# ProxSensorType1.net
KiCad netlist of a schematic drawn in Altium Designer
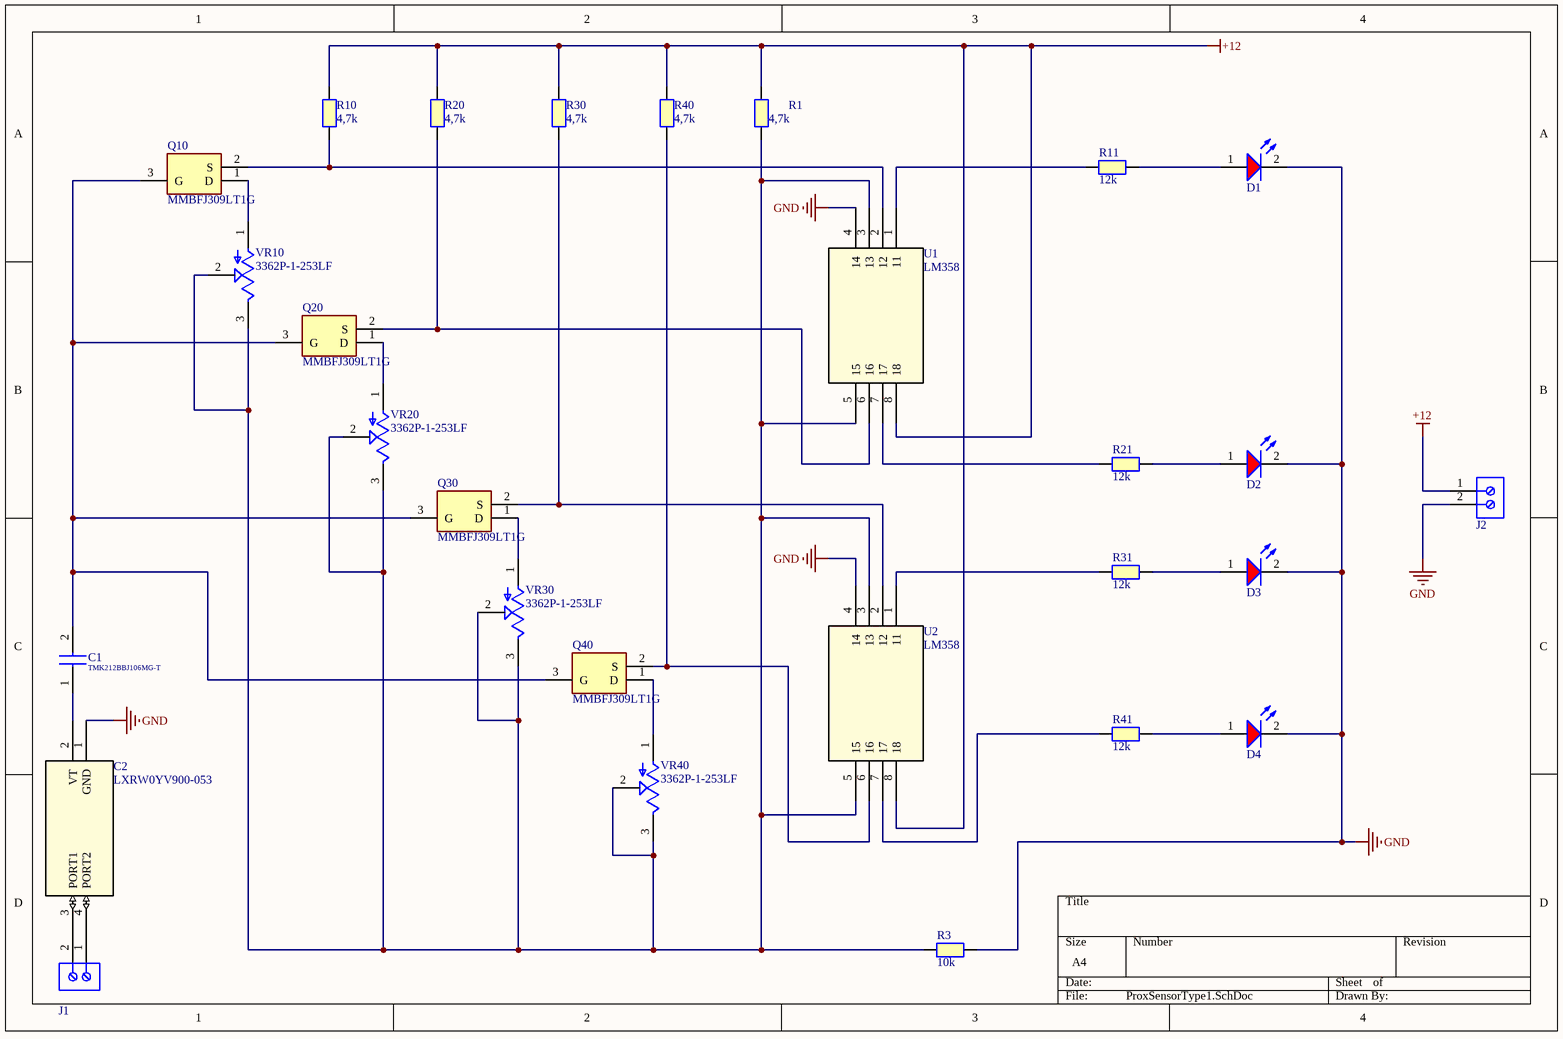
[diagram p0: ProxSensorType1.SchDoc]

(export (version "E")
  (design (tool "Eeschema 10.0.6"))
  (components
    (comp (ref "C1")
      (value "TMK212BBJ106MG-T")
      (footprint "Sensor_1:CAPC2012X65N")
      (description "Capacitor")
      (fields (field (name "MOUSER PART NUMBER") "963-TMK212BBJ106MG-T"))
      (libsource (lib "Sensor_1") (part "TMK212BBJ106MG-T"))
    )
    (comp (ref "C2")
      (value "LXRW0YV900-053")
      (footprint "LXRW-0Y_MUR-M")
      (description "Cap trimmer (variable capacitor)")
      (fields (field (name "COPYRIGHT") "Copyright (C) 2023 Ultra Librarian. All rights reserved."))
      (libsource (lib "Sensor_1") (part "LXRW0YV900-053"))
    )
    (comp (ref "D1")
      (value "Super Red, 2.1V, 40°")
      (footprint "WL-TMRC_D5.9H8.7")
      (description "WL-TMRC Mono-color Round Color, THT, D5.9 x H8.7mm, Super Red, 2.1V, 40°")
      (fields
        (field (name "MANUFACTURER PART NUMBER") "151051SS04000")
        (field (name "MANUFACTURER") "Wurth Elektronik")
      )
      (libsource (lib "Sensor_1") (part "LED_151051SS04000"))
    )
    (comp (ref "D2")
      (value "Super Red, 2.1V, 40°")
      (footprint "WL-TMRC_D5.9H8.7")
      (description "WL-TMRC Mono-color Round Color, THT, D5.9 x H8.7mm, Super Red, 2.1V, 40°")
      (fields
        (field (name "MANUFACTURER PART NUMBER") "151051SS04000")
        (field (name "MANUFACTURER") "Wurth Elektronik")
      )
      (libsource (lib "Sensor_1") (part "LED_151051SS04000"))
    )
    (comp (ref "D3")
      (value "Super Red, 2.1V, 40°")
      (footprint "WL-TMRC_D5.9H8.7")
      (description "WL-TMRC Mono-color Round Color, THT, D5.9 x H8.7mm, Super Red, 2.1V, 40°")
      (fields
        (field (name "MANUFACTURER PART NUMBER") "151051SS04000")
        (field (name "MANUFACTURER") "Wurth Elektronik")
      )
      (libsource (lib "Sensor_1") (part "LED_151051SS04000"))
    )
    (comp (ref "D4")
      (value "Super Red, 2.1V, 40°")
      (footprint "WL-TMRC_D5.9H8.7")
      (description "WL-TMRC Mono-color Round Color, THT, D5.9 x H8.7mm, Super Red, 2.1V, 40°")
      (fields
        (field (name "MANUFACTURER PART NUMBER") "151051SS04000")
        (field (name "MANUFACTURER") "Wurth Elektronik")
      )
      (libsource (lib "Sensor_1") (part "LED_151051SS04000"))
    )
    (comp (ref "J1")
      (value "691210910002")
      (footprint "691210910002")
      (description "WR-TBL Series 2109 Horizontal Entry, THT, pitch 2.54mm, 2p")
      (fields (field (name "MANUFACTURER") "Wurth Elektronik"))
      (libsource (lib "Sensor_1") (part "691210910002"))
    )
    (comp (ref "J2")
      (value "691210910002")
      (footprint "691210910002")
      (description "WR-TBL Series 2109 Horizontal Entry, THT, pitch 2.54mm, 2p")
      (fields (field (name "MANUFACTURER") "Wurth Elektronik"))
      (libsource (lib "Sensor_1") (part "691210910002"))
    )
    (comp (ref "Q10")
      (value "MMBFJ309LT1G")
      (footprint "SamacSys:SOT96P237X111-3N")
      (description "Transistor")
      (fields (field (name "MOUSER PART NUMBER") "863-MMBFJ309LT1G"))
      (libsource (lib "*") (part "MMBFJ309LT1G"))
    )
    (comp (ref "Q20")
      (value "MMBFJ309LT1G")
      (footprint "SamacSys:SOT96P237X111-3N")
      (description "Transistor")
      (fields (field (name "MOUSER PART NUMBER") "863-MMBFJ309LT1G"))
      (libsource (lib "*") (part "MMBFJ309LT1G"))
    )
    (comp (ref "Q30")
      (value "MMBFJ309LT1G")
      (footprint "SamacSys:SOT96P237X111-3N")
      (description "Transistor")
      (fields (field (name "MOUSER PART NUMBER") "863-MMBFJ309LT1G"))
      (libsource (lib "*") (part "MMBFJ309LT1G"))
    )
    (comp (ref "Q40")
      (value "MMBFJ309LT1G")
      (footprint "SamacSys:SOT96P237X111-3N")
      (description "Transistor")
      (fields (field (name "MOUSER PART NUMBER") "863-MMBFJ309LT1G"))
      (libsource (lib "*") (part "MMBFJ309LT1G"))
    )
    (comp (ref "R1")
      (value "4,7k")
      (footprint "RESC2012X50N")
      (description "4,7k Resistor 0805")
      (fields (field (name "PART NUMBER") "TNPW080510K0BETA") (field (name "MANUFACTURER") "Vishay Dale"))
      (libsource (lib "") (part "RESISTOR 0805_1"))
    )
    (comp (ref "R3")
      (value "10k")
      (footprint "RESC2012X50N")
      (description "10k Resistor 0805")
      (fields (field (name "PART NUMBER") "TNPW080510K0BETA") (field (name "MANUFACTURER") "Vishay Dale"))
      (libsource (lib "Sensor_1") (part "RESISTOR 0805"))
    )
    (comp (ref "R10")
      (value "4,7k")
      (footprint "RESC2012X50N")
      (description "4,7k Resistor 0805")
      (fields (field (name "PART NUMBER") "TNPW080510K0BETA") (field (name "MANUFACTURER") "Vishay Dale"))
      (libsource (lib "") (part "RESISTOR 0805_1"))
    )
    (comp (ref "R11")
      (value "12k")
      (footprint "RESC2012X50N")
      (description "12k Resistor 0805")
      (fields (field (name "PART NUMBER") "TNPW080510K0BETA") (field (name "MANUFACTURER") "Vishay Dale"))
      (libsource (lib "Sensor_1") (part "RESISTOR 0805"))
    )
    (comp (ref "R20")
      (value "4,7k")
      (footprint "RESC2012X50N")
      (description "4,7k Resistor 0805")
      (fields (field (name "PART NUMBER") "TNPW080510K0BETA") (field (name "MANUFACTURER") "Vishay Dale"))
      (libsource (lib "") (part "RESISTOR 0805_1"))
    )
    (comp (ref "R21")
      (value "12k")
      (footprint "RESC2012X50N")
      (description "12k Resistor 0805")
      (fields (field (name "PART NUMBER") "TNPW080510K0BETA") (field (name "MANUFACTURER") "Vishay Dale"))
      (libsource (lib "Sensor_1") (part "RESISTOR 0805"))
    )
    (comp (ref "R30")
      (value "4,7k")
      (footprint "RESC2012X50N")
      (description "4,7k Resistor 0805")
      (fields (field (name "PART NUMBER") "TNPW080510K0BETA") (field (name "MANUFACTURER") "Vishay Dale"))
      (libsource (lib "") (part "RESISTOR 0805_1"))
    )
    (comp (ref "R31")
      (value "12k")
      (footprint "RESC2012X50N")
      (description "12k Resistor 0805")
      (fields (field (name "PART NUMBER") "TNPW080510K0BETA") (field (name "MANUFACTURER") "Vishay Dale"))
      (libsource (lib "Sensor_1") (part "RESISTOR 0805"))
    )
    (comp (ref "R40")
      (value "4,7k")
      (footprint "RESC2012X50N")
      (description "4,7k Resistor 0805")
      (fields (field (name "PART NUMBER") "TNPW080510K0BETA") (field (name "MANUFACTURER") "Vishay Dale"))
      (libsource (lib "") (part "RESISTOR 0805_1"))
    )
    (comp (ref "R41")
      (value "12k")
      (footprint "RESC2012X50N")
      (description "12k Resistor 0805")
      (fields (field (name "PART NUMBER") "TNPW080510K0BETA") (field (name "MANUFACTURER") "Vishay Dale"))
      (libsource (lib "Sensor_1") (part "RESISTOR 0805"))
    )
    (comp (ref "U1")
      (value "LM358")
      (footprint "DIP8_300")
      (description "Texas instruments LM358 opamp")
      (fields (field (name "COPYRIGHT") "Copyright (C) 2023 Ultra Librarian. All rights reserved."))
      (libsource (lib "Sensor_1") (part "LM358"))
    )
    (comp (ref "U2")
      (value "LM358")
      (footprint "DIP8_300")
      (description "Texas instruments LM358 opamp")
      (fields (field (name "COPYRIGHT") "Copyright (C) 2023 Ultra Librarian. All rights reserved."))
      (libsource (lib "Sensor_1") (part "LM358"))
    )
    (comp (ref "VR10")
      (value "3362P-1-253LF")
      (footprint "Sensor_1:TRIM_3362P-1-253LF")
      (description "25 kOhms 0.5W, 1/2W PC Pins Through Hole Trimmer Potentiometer Cermet 1 Turn Top Adjustment")
      (fields (field (name "MF") "Bourns"))
      (libsource (lib "Sensor_1") (part "3362P-1-253LF"))
    )
    (comp (ref "VR20")
      (value "3362P-1-253LF")
      (footprint "Sensor_1:TRIM_3362P-1-253LF")
      (description "25 kOhms 0.5W, 1/2W PC Pins Through Hole Trimmer Potentiometer Cermet 1 Turn Top Adjustment")
      (fields (field (name "MF") "Bourns"))
      (libsource (lib "Sensor_1") (part "3362P-1-253LF"))
    )
    (comp (ref "VR30")
      (value "3362P-1-253LF")
      (footprint "Sensor_1:TRIM_3362P-1-253LF")
      (description "25 kOhms 0.5W, 1/2W PC Pins Through Hole Trimmer Potentiometer Cermet 1 Turn Top Adjustment")
      (fields (field (name "MF") "Bourns"))
      (libsource (lib "Sensor_1") (part "3362P-1-253LF"))
    )
    (comp (ref "VR40")
      (value "3362P-1-253LF")
      (footprint "Sensor_1:TRIM_3362P-1-253LF")
      (description "25 kOhms 0.5W, 1/2W PC Pins Through Hole Trimmer Potentiometer Cermet 1 Turn Top Adjustment")
      (fields (field (name "MF") "Bourns"))
      (libsource (lib "Sensor_1") (part "3362P-1-253LF"))
    )
  )
  (nets
    (net (code "1") (name "+12") (class "Default")
      (node (ref "J2") (pin "1") (pinfunction "1_1") (pintype "passive"))
      (node (ref "R1") (pin "2") (pinfunction "2_2") (pintype "passive"))
      (node (ref "R10") (pin "2") (pinfunction "2_2") (pintype "passive"))
      (node (ref "R20") (pin "2") (pinfunction "2_2") (pintype "passive"))
      (node (ref "R30") (pin "2") (pinfunction "2_2") (pintype "passive"))
      (node (ref "R40") (pin "2") (pinfunction "2_2") (pintype "passive"))
      (node (ref "U1") (pin "8") (pinfunction "18_8") (pintype "passive"))
      (node (ref "U2") (pin "8") (pinfunction "18_8") (pintype "passive"))
    )
    (net (code "2") (name "GND") (class "Default")
      (node (ref "C2") (pin "1") (pinfunction "GND_1") (pintype "passive"))
      (node (ref "D1") (pin "2") (pinfunction "K_2") (pintype "passive"))
      (node (ref "D2") (pin "2") (pinfunction "K_2") (pintype "passive"))
      (node (ref "D3") (pin "2") (pinfunction "K_2") (pintype "passive"))
      (node (ref "D4") (pin "2") (pinfunction "K_2") (pintype "passive"))
      (node (ref "J2") (pin "2") (pinfunction "2_2") (pintype "passive"))
      (node (ref "R3") (pin "1") (pinfunction "1_1") (pintype "passive"))
      (node (ref "U1") (pin "4") (pinfunction "14_4") (pintype "passive"))
      (node (ref "U2") (pin "4") (pinfunction "14_4") (pintype "passive"))
    )
    (net (code "3") (name "Net-(C2-PORT1)") (class "Default")
      (node (ref "C2") (pin "3") (pinfunction "PORT1_3") (pintype "bidirectional"))
      (node (ref "J1") (pin "2") (pinfunction "2_2") (pintype "passive"))
    )
    (net (code "4") (name "Net-(C2-PORT2)") (class "Default")
      (node (ref "C2") (pin "4") (pinfunction "PORT2_4") (pintype "bidirectional"))
      (node (ref "J1") (pin "1") (pinfunction "1_1") (pintype "passive"))
    )
    (net (code "5") (name "Net-(C2-VT)") (class "Default")
      (node (ref "C1") (pin "1") (pinfunction "1_1") (pintype "passive"))
      (node (ref "C2") (pin "2") (pinfunction "VT_2") (pintype "passive"))
    )
    (net (code "6") (name "Net-(D1-A)") (class "Default")
      (node (ref "D1") (pin "1") (pinfunction "A_1") (pintype "passive"))
      (node (ref "R11") (pin "1") (pinfunction "1_1") (pintype "passive"))
    )
    (net (code "7") (name "Net-(D2-A)") (class "Default")
      (node (ref "D2") (pin "1") (pinfunction "A_1") (pintype "passive"))
      (node (ref "R21") (pin "1") (pinfunction "1_1") (pintype "passive"))
    )
    (net (code "8") (name "Net-(D3-A)") (class "Default")
      (node (ref "D3") (pin "1") (pinfunction "A_1") (pintype "passive"))
      (node (ref "R31") (pin "1") (pinfunction "1_1") (pintype "passive"))
    )
    (net (code "9") (name "Net-(D4-A)") (class "Default")
      (node (ref "D4") (pin "1") (pinfunction "A_1") (pintype "passive"))
      (node (ref "R41") (pin "1") (pinfunction "1_1") (pintype "passive"))
    )
    (net (code "10") (name "Net-(Q10-D)") (class "Default")
      (node (ref "Q10") (pin "1") (pinfunction "D_1") (pintype "passive"))
      (node (ref "VR10") (pin "1") (pinfunction "CCW_1") (pintype "passive"))
    )
    (net (code "11") (name "Net-(Q10-G)") (class "Default")
      (node (ref "C1") (pin "2") (pinfunction "2_2") (pintype "passive"))
      (node (ref "Q10") (pin "3") (pinfunction "G_3") (pintype "passive"))
      (node (ref "Q20") (pin "3") (pinfunction "G_3") (pintype "passive"))
      (node (ref "Q30") (pin "3") (pinfunction "G_3") (pintype "passive"))
      (node (ref "Q40") (pin "3") (pinfunction "G_3") (pintype "passive"))
    )
    (net (code "12") (name "Net-(Q10-S)") (class "Default")
      (node (ref "Q10") (pin "2") (pinfunction "S_2") (pintype "passive"))
      (node (ref "R10") (pin "1") (pinfunction "1_1") (pintype "passive"))
      (node (ref "U1") (pin "2") (pinfunction "12_2") (pintype "passive"))
    )
    (net (code "13") (name "Net-(Q20-D)") (class "Default")
      (node (ref "Q20") (pin "1") (pinfunction "D_1") (pintype "passive"))
      (node (ref "VR20") (pin "1") (pinfunction "CCW_1") (pintype "passive"))
    )
    (net (code "14") (name "Net-(Q20-S)") (class "Default")
      (node (ref "Q20") (pin "2") (pinfunction "S_2") (pintype "passive"))
      (node (ref "R20") (pin "1") (pinfunction "1_1") (pintype "passive"))
      (node (ref "U1") (pin "6") (pinfunction "16_6") (pintype "passive"))
    )
    (net (code "15") (name "Net-(Q30-D)") (class "Default")
      (node (ref "Q30") (pin "1") (pinfunction "D_1") (pintype "passive"))
      (node (ref "VR30") (pin "1") (pinfunction "CCW_1") (pintype "passive"))
    )
    (net (code "16") (name "Net-(Q30-S)") (class "Default")
      (node (ref "Q30") (pin "2") (pinfunction "S_2") (pintype "passive"))
      (node (ref "R30") (pin "1") (pinfunction "1_1") (pintype "passive"))
      (node (ref "U2") (pin "2") (pinfunction "12_2") (pintype "passive"))
    )
    (net (code "17") (name "Net-(Q40-D)") (class "Default")
      (node (ref "Q40") (pin "1") (pinfunction "D_1") (pintype "passive"))
      (node (ref "VR40") (pin "1") (pinfunction "CCW_1") (pintype "passive"))
    )
    (net (code "18") (name "Net-(Q40-S)") (class "Default")
      (node (ref "Q40") (pin "2") (pinfunction "S_2") (pintype "passive"))
      (node (ref "R40") (pin "1") (pinfunction "1_1") (pintype "passive"))
      (node (ref "U2") (pin "6") (pinfunction "16_6") (pintype "passive"))
    )
    (net (code "19") (name "Net-(U1-11)") (class "Default")
      (node (ref "R11") (pin "2") (pinfunction "2_2") (pintype "passive"))
      (node (ref "U1") (pin "1") (pinfunction "11_1") (pintype "passive"))
    )
    (net (code "20") (name "Net-(U1-13)") (class "Default")
      (node (ref "R1") (pin "1") (pinfunction "1_1") (pintype "passive"))
      (node (ref "R3") (pin "2") (pinfunction "2_2") (pintype "passive"))
      (node (ref "U1") (pin "3") (pinfunction "13_3") (pintype "passive"))
      (node (ref "U1") (pin "5") (pinfunction "15_5") (pintype "passive"))
      (node (ref "U2") (pin "3") (pinfunction "13_3") (pintype "passive"))
      (node (ref "U2") (pin "5") (pinfunction "15_5") (pintype "passive"))
      (node (ref "VR10") (pin "2") (pinfunction "WIPER_2") (pintype "passive"))
      (node (ref "VR10") (pin "3") (pinfunction "CW_3") (pintype "passive"))
      (node (ref "VR20") (pin "2") (pinfunction "WIPER_2") (pintype "passive"))
      (node (ref "VR20") (pin "3") (pinfunction "CW_3") (pintype "passive"))
      (node (ref "VR30") (pin "2") (pinfunction "WIPER_2") (pintype "passive"))
      (node (ref "VR30") (pin "3") (pinfunction "CW_3") (pintype "passive"))
      (node (ref "VR40") (pin "2") (pinfunction "WIPER_2") (pintype "passive"))
      (node (ref "VR40") (pin "3") (pinfunction "CW_3") (pintype "passive"))
    )
    (net (code "21") (name "Net-(U1-17)") (class "Default")
      (node (ref "R21") (pin "2") (pinfunction "2_2") (pintype "passive"))
      (node (ref "U1") (pin "7") (pinfunction "17_7") (pintype "passive"))
    )
    (net (code "22") (name "Net-(U2-11)") (class "Default")
      (node (ref "R31") (pin "2") (pinfunction "2_2") (pintype "passive"))
      (node (ref "U2") (pin "1") (pinfunction "11_1") (pintype "passive"))
    )
    (net (code "23") (name "Net-(U2-17)") (class "Default")
      (node (ref "R41") (pin "2") (pinfunction "2_2") (pintype "passive"))
      (node (ref "U2") (pin "7") (pinfunction "17_7") (pintype "passive"))
    )
  )
)
